# ROS-Robot-Controller.net
KiCad netlist of a schematic drawn in Altium Designer
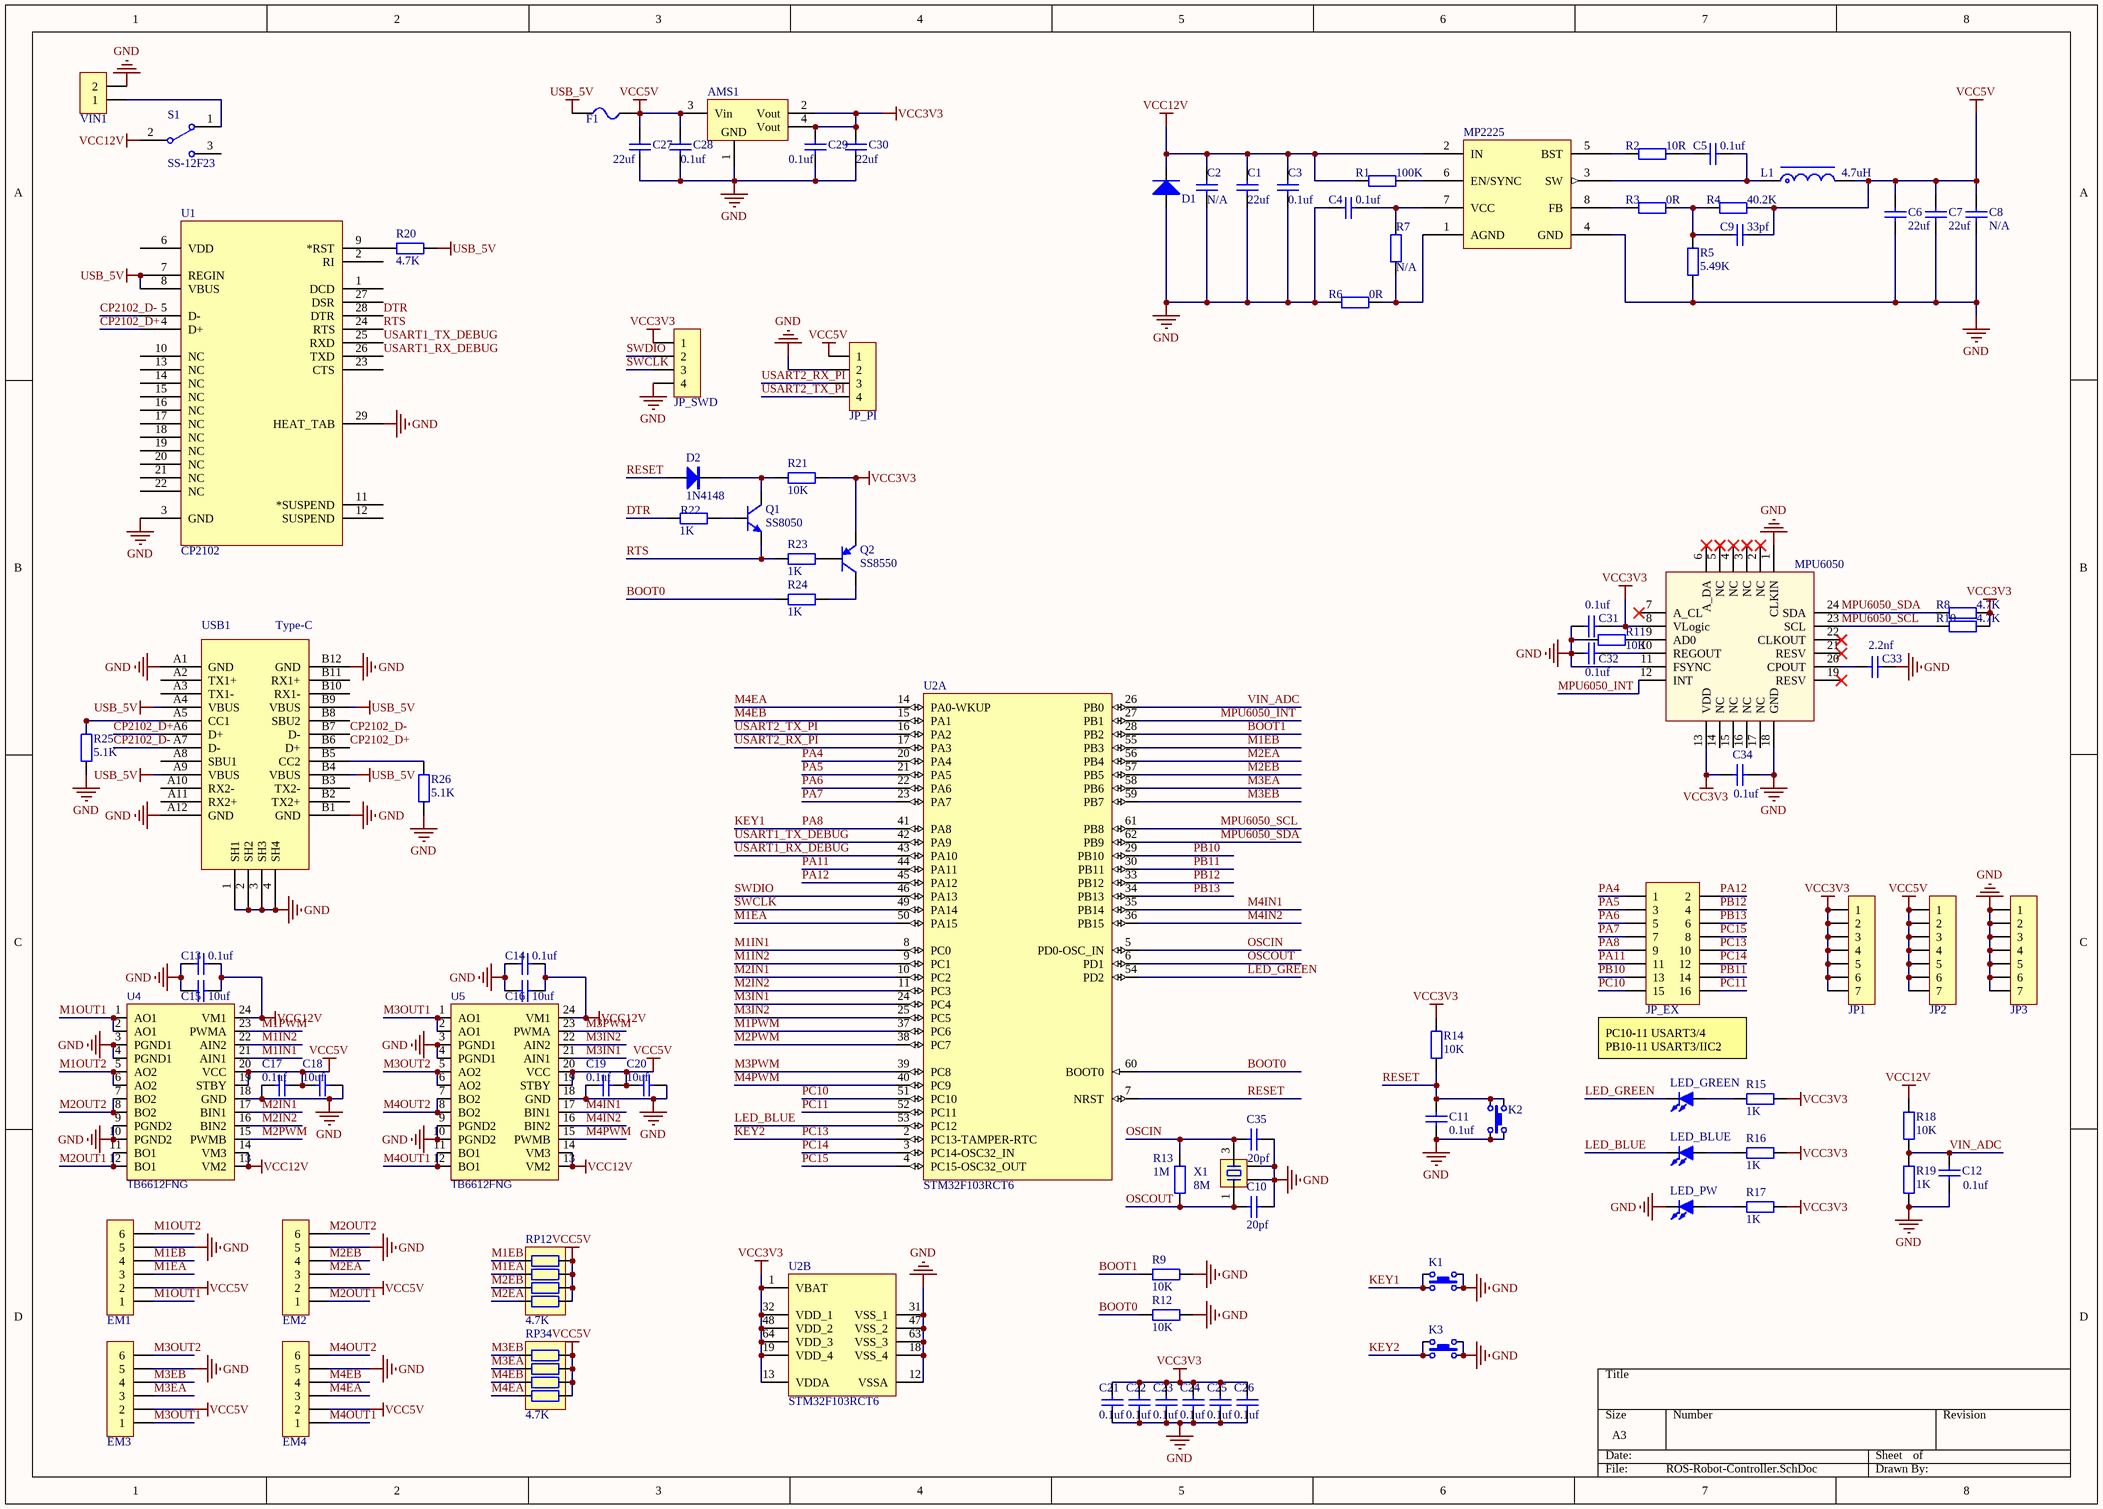
[diagram p0: ROS-Robot-Controller.SchDoc]

(export (version "E")
  (design (tool "Eeschema 10.0.6"))
  (components
    (comp (ref "AMS1")
      (value "AMS1117-3V3")
      (footprint "SOT223_L")
      (description "三端稳压芯片")
      (libsource (lib "1.1 - 电源类芯片") (part "AMS1117"))
    )
    (comp (ref "C1")
      (value "22uf")
      (footprint "C1206_L")
      (description "贴片电容")
      (libsource (lib "0.1 - 电阻-电容-电感-电位器") (part "C"))
    )
    (comp (ref "C2")
      (value "N/A")
      (footprint "C1206_L")
      (description "贴片电容")
      (libsource (lib "0.1 - 电阻-电容-电感-电位器") (part "C"))
    )
    (comp (ref "C3")
      (value "0.1uf")
      (footprint "C0603_L")
      (description "贴片电容")
      (libsource (lib "0.1 - 电阻-电容-电感-电位器") (part "C"))
    )
    (comp (ref "C4")
      (value "0.1uf")
      (footprint "C0603_L")
      (description "贴片电容")
      (libsource (lib "0.1 - 电阻-电容-电感-电位器") (part "C"))
    )
    (comp (ref "C5")
      (value "0.1uf")
      (footprint "C0603_L")
      (description "贴片电容")
      (libsource (lib "0.1 - 电阻-电容-电感-电位器") (part "C"))
    )
    (comp (ref "C6")
      (value "22uf")
      (footprint "C0805_L")
      (description "贴片电容")
      (libsource (lib "0.1 - 电阻-电容-电感-电位器") (part "C"))
    )
    (comp (ref "C7")
      (value "22uf")
      (footprint "C0805_L")
      (description "贴片电容")
      (libsource (lib "0.1 - 电阻-电容-电感-电位器") (part "C"))
    )
    (comp (ref "C8")
      (value "N/A")
      (footprint "C0805_L")
      (description "贴片电容")
      (libsource (lib "0.1 - 电阻-电容-电感-电位器") (part "C"))
    )
    (comp (ref "C9")
      (value "33pf")
      (footprint "C0603_L")
      (description "贴片电容")
      (libsource (lib "0.1 - 电阻-电容-电感-电位器") (part "C"))
    )
    (comp (ref "C10")
      (value "20pf")
      (footprint "C0402_L")
      (description "贴片电容")
      (libsource (lib "0.1 - 电阻-电容-电感-电位器") (part "C"))
    )
    (comp (ref "C11")
      (value "0.1uf")
      (footprint "C0402_L")
      (description "贴片电容")
      (libsource (lib "0.1 - 电阻-电容-电感-电位器") (part "C"))
    )
    (comp (ref "C12")
      (value "0.1uf")
      (footprint "C0603_L")
      (description "贴片电容")
      (libsource (lib "0.1 - 电阻-电容-电感-电位器") (part "C"))
    )
    (comp (ref "C13")
      (value "0.1uf")
      (footprint "C0603_L")
      (description "贴片电容")
      (libsource (lib "0.1 - 电阻-电容-电感-电位器") (part "C"))
    )
    (comp (ref "C14")
      (value "0.1uf")
      (footprint "C0603_L")
      (description "贴片电容")
      (libsource (lib "0.1 - 电阻-电容-电感-电位器") (part "C"))
    )
    (comp (ref "C15")
      (value "10uf")
      (footprint "C0603_L")
      (description "贴片电容")
      (libsource (lib "0.1 - 电阻-电容-电感-电位器") (part "C"))
    )
    (comp (ref "C16")
      (value "10uf")
      (footprint "C0603_L")
      (description "贴片电容")
      (libsource (lib "0.1 - 电阻-电容-电感-电位器") (part "C"))
    )
    (comp (ref "C17")
      (value "0.1uf")
      (footprint "C0402_L")
      (description "贴片电容")
      (libsource (lib "0.1 - 电阻-电容-电感-电位器") (part "C"))
    )
    (comp (ref "C18")
      (value "10uf")
      (footprint "C0402_L")
      (description "贴片电容")
      (libsource (lib "0.1 - 电阻-电容-电感-电位器") (part "C"))
    )
    (comp (ref "C19")
      (value "0.1uf")
      (footprint "C0402_L")
      (description "贴片电容")
      (libsource (lib "0.1 - 电阻-电容-电感-电位器") (part "C"))
    )
    (comp (ref "C20")
      (value "10uf")
      (footprint "C0402_L")
      (description "贴片电容")
      (libsource (lib "0.1 - 电阻-电容-电感-电位器") (part "C"))
    )
    (comp (ref "C21")
      (value "0.1uf")
      (footprint "C0402_L")
      (description "贴片电容")
      (libsource (lib "0.1 - 电阻-电容-电感-电位器") (part "C"))
    )
    (comp (ref "C22")
      (value "0.1uf")
      (footprint "C0402_L")
      (description "贴片电容")
      (libsource (lib "0.1 - 电阻-电容-电感-电位器") (part "C"))
    )
    (comp (ref "C23")
      (value "0.1uf")
      (footprint "C0402_L")
      (description "贴片电容")
      (libsource (lib "0.1 - 电阻-电容-电感-电位器") (part "C"))
    )
    (comp (ref "C24")
      (value "0.1uf")
      (footprint "C0402_L")
      (description "贴片电容")
      (libsource (lib "0.1 - 电阻-电容-电感-电位器") (part "C"))
    )
    (comp (ref "C25")
      (value "0.1uf")
      (footprint "C0402_L")
      (description "贴片电容")
      (libsource (lib "0.1 - 电阻-电容-电感-电位器") (part "C"))
    )
    (comp (ref "C26")
      (value "0.1uf")
      (footprint "C0402_L")
      (description "贴片电容")
      (libsource (lib "0.1 - 电阻-电容-电感-电位器") (part "C"))
    )
    (comp (ref "C27")
      (value "22uf")
      (footprint "C0603_L")
      (description "贴片电容")
      (libsource (lib "0.1 - 电阻-电容-电感-电位器") (part "C"))
    )
    (comp (ref "C28")
      (value "0.1uf")
      (footprint "C0603_L")
      (description "贴片电容")
      (libsource (lib "0.1 - 电阻-电容-电感-电位器") (part "C"))
    )
    (comp (ref "C29")
      (value "0.1uf")
      (footprint "C0603_L")
      (description "贴片电容")
      (libsource (lib "0.1 - 电阻-电容-电感-电位器") (part "C"))
    )
    (comp (ref "C30")
      (value "22uf")
      (footprint "C0603_L")
      (description "贴片电容")
      (libsource (lib "0.1 - 电阻-电容-电感-电位器") (part "C"))
    )
    (comp (ref "C31")
      (value "0.1uf")
      (footprint "C0402_L")
      (description "贴片电容")
      (libsource (lib "0.1 - 电阻-电容-电感-电位器") (part "C"))
    )
    (comp (ref "C32")
      (value "0.1uf")
      (footprint "C0402_L")
      (description "贴片电容")
      (libsource (lib "0.1 - 电阻-电容-电感-电位器") (part "C"))
    )
    (comp (ref "C33")
      (value "2.2nf")
      (footprint "C0402_L")
      (description "贴片电容")
      (libsource (lib "0.1 - 电阻-电容-电感-电位器") (part "C"))
    )
    (comp (ref "C34")
      (value "0.1uf")
      (footprint "C0402_L")
      (description "贴片电容")
      (libsource (lib "0.1 - 电阻-电容-电感-电位器") (part "C"))
    )
    (comp (ref "C35")
      (value "20pf")
      (footprint "C0402_L")
      (description "贴片电容")
      (libsource (lib "0.1 - 电阻-电容-电感-电位器") (part "C"))
    )
    (comp (ref "D1")
      (value "SMAJ12A")
      (footprint "SMA")
      (description "TVS通用")
      (libsource (lib "0.2 - 二极管-TVS-整流桥") (part "TVS"))
    )
    (comp (ref "D2")
      (value "1N4148")
      (footprint "SOD-323")
      (description "开关二极管")
      (libsource (lib "0.2 - 二极管-TVS-整流桥") (part "1N4148"))
    )
    (comp (ref "EM1")
      (value "HDR-1X6")
      (footprint "XH2.54-LI-6P")
      (description "6P接插件")
      (libsource (lib "5.4 - 接插件-脚距2.54 (100mil) ") (part "Header 6"))
    )
    (comp (ref "EM2")
      (value "HDR-1X6")
      (footprint "XH2.54-LI-6P")
      (description "6P接插件")
      (libsource (lib "5.4 - 接插件-脚距2.54 (100mil) ") (part "Header 6"))
    )
    (comp (ref "EM3")
      (value "HDR-1X6")
      (footprint "XH2.54-LI-6P")
      (description "6P接插件")
      (libsource (lib "5.4 - 接插件-脚距2.54 (100mil) ") (part "Header 6"))
    )
    (comp (ref "EM4")
      (value "HDR-1X6")
      (footprint "XH2.54-LI-6P")
      (description "6P接插件")
      (libsource (lib "5.4 - 接插件-脚距2.54 (100mil) ") (part "Header 6"))
    )
    (comp (ref "F1")
      (value "MSMD200-8V 2A")
      (footprint "FU 0603")
      (description "贴片保险丝")
      (libsource (lib "0.5 - 保险丝-晶振-光耦") (part "FU"))
    )
    (comp (ref "JP1")
      (value "HDR-1X7")
      (footprint "HDR2.54-LI-7P")
      (description "7P接插件")
      (libsource (lib "5.4 - 接插件-脚距2.54 (100mil) ") (part "Header 7"))
    )
    (comp (ref "JP2")
      (value "HDR-1X7")
      (footprint "HDR2.54-LI-7P")
      (description "7P接插件")
      (libsource (lib "5.4 - 接插件-脚距2.54 (100mil) ") (part "Header 7"))
    )
    (comp (ref "JP3")
      (value "HDR-1X7")
      (footprint "HDR2.54-LI-7P")
      (description "7P接插件")
      (libsource (lib "5.4 - 接插件-脚距2.54 (100mil) ") (part "Header 7"))
    )
    (comp (ref "JP_EX")
      (value "Header 8X2")
      (footprint "HDR2.54-LI-2x8P")
      (description "8*2P接插件")
      (libsource (lib "5.4 - 接插件-脚距2.54 (100mil) ") (part "Header 8X2"))
    )
    (comp (ref "JP_PI")
      (value "HDR-1X4")
      (footprint "HDR2.54-LI-4P")
      (description "4P接插件")
      (libsource (lib "5.4 - 接插件-脚距2.54 (100mil) ") (part "Header 4"))
    )
    (comp (ref "JP_SWD")
      (value "HDR-1X4")
      (footprint "XH2.54-WI-4P")
      (description "4P接插件")
      (libsource (lib "5.4 - 接插件-脚距2.54 (100mil) ") (part "Header 4"))
    )
    (comp (ref "K1")
      (value "TACT 4P")
      (footprint "SW-SMD_4P-L4.2-W3.3-P2.15-LS5.1")
      (description "Button")
      (libsource (lib "KitSprout") (part "ButtonTACT"))
    )
    (comp (ref "K2")
      (value "TACT 4P")
      (footprint "SW-SMD_4P-L4.2-W3.3-P2.15-LS5.1")
      (description "Button")
      (libsource (lib "KitSprout") (part "ButtonTACT"))
    )
    (comp (ref "K3")
      (value "TACT 4P")
      (footprint "SW-SMD_4P-L4.2-W3.3-P2.15-LS5.1")
      (description "Button")
      (libsource (lib "KitSprout") (part "ButtonTACT"))
    )
    (comp (ref "L1")
      (value "4.7uH")
      (footprint "L-SMD-0630")
      (description "一体成型电感")
      (libsource (lib "0.1 - 电阻-电容-电感-电位器") (part "L-Molding Choke"))
    )
    (comp (ref "LED_BLUE")
      (value "红色")
      (footprint "LED_0402_RED")
      (description "贴片LED")
      (libsource (lib "0.3 - LED发光二极管") (part "LED-SMD"))
    )
    (comp (ref "LED_GREEN")
      (value "红色")
      (footprint "LED_0402_RED")
      (description "贴片LED")
      (libsource (lib "0.3 - LED发光二极管") (part "LED-SMD"))
    )
    (comp (ref "LED_PW")
      (value "红色")
      (footprint "LED_0402_RED")
      (description "贴片LED")
      (libsource (lib "0.3 - LED发光二极管") (part "LED-SMD"))
    )
    (comp (ref "MP2225")
      (value "MP2225")
      (footprint "TSOT23-8_MP2225_MNP")
      (libsource (lib "MP2225") (part "MP2225修改版"))
    )
    (comp (ref "Q1")
      (value "SS8050")
      (footprint "SOT23-3N")
      (description "高频放大-NPN型")
      (libsource (lib "0.4 - 三极管-场效应管-可控硅") (part "8050-SMD"))
    )
    (comp (ref "Q2")
      (value "SS8550")
      (footprint "SOT23-3N")
      (description "高频放大-PNP型")
      (libsource (lib "0.4 - 三极管-场效应管-可控硅") (part "8550-SMD"))
    )
    (comp (ref "R1")
      (value "100K")
      (footprint "R0603_L")
      (description "贴片电阻")
      (libsource (lib "0.1 - 电阻-电容-电感-电位器") (part "R"))
    )
    (comp (ref "R2")
      (value "10R")
      (footprint "R0603_L")
      (description "贴片电阻")
      (libsource (lib "0.1 - 电阻-电容-电感-电位器") (part "R"))
    )
    (comp (ref "R3")
      (value "0R")
      (footprint "R0603_L")
      (description "贴片电阻")
      (libsource (lib "0.1 - 电阻-电容-电感-电位器") (part "R"))
    )
    (comp (ref "R4")
      (value "40.2K")
      (footprint "R0603_L")
      (description "贴片电阻")
      (libsource (lib "0.1 - 电阻-电容-电感-电位器") (part "R"))
    )
    (comp (ref "R5")
      (value "5.49K")
      (footprint "R0603_L")
      (description "贴片电阻")
      (libsource (lib "0.1 - 电阻-电容-电感-电位器") (part "R"))
    )
    (comp (ref "R6")
      (value "0R")
      (footprint "R0603_L")
      (description "贴片电阻")
      (libsource (lib "0.1 - 电阻-电容-电感-电位器") (part "R"))
    )
    (comp (ref "R7")
      (value "N/A")
      (footprint "R0603_L")
      (description "贴片电阻")
      (libsource (lib "0.1 - 电阻-电容-电感-电位器") (part "R"))
    )
    (comp (ref "R8")
      (value "4.7K")
      (footprint "R0402_L")
      (description "贴片电阻")
      (libsource (lib "0.1 - 电阻-电容-电感-电位器") (part "R"))
    )
    (comp (ref "R9")
      (value "10K")
      (footprint "R0402_L")
      (description "贴片电阻")
      (libsource (lib "0.1 - 电阻-电容-电感-电位器") (part "R"))
    )
    (comp (ref "R10")
      (value "4.7K")
      (footprint "R0402_L")
      (description "贴片电阻")
      (libsource (lib "0.1 - 电阻-电容-电感-电位器") (part "R"))
    )
    (comp (ref "R11")
      (value "10K")
      (footprint "R0402_L")
      (description "贴片电阻")
      (libsource (lib "0.1 - 电阻-电容-电感-电位器") (part "R"))
    )
    (comp (ref "R12")
      (value "10K")
      (footprint "R0402_L")
      (description "贴片电阻")
      (libsource (lib "0.1 - 电阻-电容-电感-电位器") (part "R"))
    )
    (comp (ref "R13")
      (value "1M")
      (footprint "R0402_L")
      (description "贴片电阻")
      (libsource (lib "0.1 - 电阻-电容-电感-电位器") (part "R"))
    )
    (comp (ref "R14")
      (value "10K")
      (footprint "R0402_L")
      (description "贴片电阻")
      (libsource (lib "0.1 - 电阻-电容-电感-电位器") (part "R"))
    )
    (comp (ref "R15")
      (value "1K")
      (footprint "R0402_L")
      (description "贴片电阻")
      (libsource (lib "0.1 - 电阻-电容-电感-电位器") (part "R"))
    )
    (comp (ref "R16")
      (value "1K")
      (footprint "R0402_L")
      (description "贴片电阻")
      (libsource (lib "0.1 - 电阻-电容-电感-电位器") (part "R"))
    )
    (comp (ref "R17")
      (value "1K")
      (footprint "R0402_L")
      (description "贴片电阻")
      (libsource (lib "0.1 - 电阻-电容-电感-电位器") (part "R"))
    )
    (comp (ref "R18")
      (value "10K")
      (footprint "R0603_L")
      (description "贴片电阻")
      (libsource (lib "0.1 - 电阻-电容-电感-电位器") (part "R"))
    )
    (comp (ref "R19")
      (value "1K")
      (footprint "R0603_L")
      (description "贴片电阻")
      (libsource (lib "0.1 - 电阻-电容-电感-电位器") (part "R"))
    )
    (comp (ref "R20")
      (value "4.7K")
      (footprint "R0402_L")
      (description "贴片电阻")
      (libsource (lib "0.1 - 电阻-电容-电感-电位器") (part "R"))
    )
    (comp (ref "R21")
      (value "10K")
      (footprint "R0402_L")
      (description "贴片电阻")
      (libsource (lib "0.1 - 电阻-电容-电感-电位器") (part "R"))
    )
    (comp (ref "R22")
      (value "1K")
      (footprint "R0402_L")
      (description "贴片电阻")
      (libsource (lib "0.1 - 电阻-电容-电感-电位器") (part "R"))
    )
    (comp (ref "R23")
      (value "1K")
      (footprint "R0402_L")
      (description "贴片电阻")
      (libsource (lib "0.1 - 电阻-电容-电感-电位器") (part "R"))
    )
    (comp (ref "R24")
      (value "1K")
      (footprint "R0402_L")
      (description "贴片电阻")
      (libsource (lib "0.1 - 电阻-电容-电感-电位器") (part "R"))
    )
    (comp (ref "R25")
      (value "5.1K")
      (footprint "R0402_L")
      (description "贴片电阻")
      (libsource (lib "0.1 - 电阻-电容-电感-电位器") (part "R"))
    )
    (comp (ref "R26")
      (value "5.1K")
      (footprint "R0402_L")
      (description "贴片电阻")
      (libsource (lib "0.1 - 电阻-电容-电感-电位器") (part "R"))
    )
    (comp (ref "RP12")
      (value "4.7K")
      (footprint "RCA-8P4R-0402")
      (description "贴片4P排阻")
      (libsource (lib "0.1 - 电阻-电容-电感-电位器") (part "R-8P4R"))
    )
    (comp (ref "RP34")
      (value "4.7K")
      (footprint "RCA-8P4R-0402")
      (description "贴片4P排阻")
      (libsource (lib "0.1 - 电阻-电容-电感-电位器") (part "R-8P4R"))
    )
    (comp (ref "S1")
      (value "SS-12F23")
      (footprint "SS-12D10")
      (description "1路波动开关")
      (libsource (lib "0.7 - 常用按键-开关-蜂鸣器-电池-测试点") (part "SSW-1P"))
    )
    (comp (ref "U1")
      (value "CP2102")
      (footprint "QFN-28")
      (description "USB转TTL")
      (libsource (lib "mLib") (part "CP2102"))
    )
    (comp (ref "U2")
      (value "STM32F103RCT6")
      (footprint "LQFP64_N")
      (libsource (lib "2.4 - STM32 F1系列单片机") (part "STM32F103RCT6"))
    )
    (comp (ref "U3")
      (value "MPU6050")
      (footprint "QFN-24")
      (description "六轴传感器")
      (libsource (lib "mLib") (part "MPU6050"))
    )
    (comp (ref "U4")
      (value "TB6612FNG")
      (footprint "SSOP24_M")
      (description "电机驱动")
      (libsource (lib "1.0 - 常见芯片") (part "TB6612FNG"))
    )
    (comp (ref "U5")
      (value "TB6612FNG")
      (footprint "SSOP24_M")
      (description "电机驱动")
      (libsource (lib "1.0 - 常见芯片") (part "TB6612FNG"))
    )
    (comp (ref "USB1")
      (value "Type-C")
      (footprint "Type-C-TOP")
      (libsource (lib "MyPcbLib") (part "USB-Type-C-TOP"))
    )
    (comp (ref "VIN1")
      (value "HDR-1X2")
      (footprint "KF301-5.0-2P")
      (description "2P接插件")
      (libsource (lib "6.0 - 接插件-脚距5.0") (part "Header 2"))
    )
    (comp (ref "X1")
      (value "8M")
      (footprint "OSC 3225-4P")
      (description "4脚无源晶振")
      (libsource (lib "0.5 - 保险丝-晶振-光耦") (part "XTAL-4P"))
    )
  )
  (nets
    (net (code "1") (name "/BOOT0") (class "Default")
      (node (ref "R12") (pin "1") (pinfunction "1_1") (pintype "passive"))
      (node (ref "R24") (pin "2") (pinfunction "2_2") (pintype "passive"))
      (node (ref "U2") (pin "60") (pinfunction "BOOT0_60") (pintype "input"))
    )
    (net (code "2") (name "/BOOT1") (class "Default")
      (node (ref "R9") (pin "1") (pinfunction "1_1") (pintype "passive"))
      (node (ref "U2") (pin "28") (pinfunction "PB2_28") (pintype "bidirectional"))
    )
    (net (code "3") (name "/CP2102_D+") (class "Default")
      (node (ref "U1") (pin "4") (pinfunction "D+_4") (pintype "passive"))
      (node (ref "USB1") (pin "A6") (pinfunction "D+_A6") (pintype "passive"))
      (node (ref "USB1") (pin "B6") (pinfunction "D+_B6") (pintype "passive"))
    )
    (net (code "4") (name "/CP2102_D-") (class "Default")
      (node (ref "U1") (pin "5") (pinfunction "D-_5") (pintype "passive"))
      (node (ref "USB1") (pin "A7") (pinfunction "D-_A7") (pintype "passive"))
      (node (ref "USB1") (pin "B7") (pinfunction "D-_B7") (pintype "passive"))
    )
    (net (code "5") (name "/DTR") (class "Default")
      (node (ref "R22") (pin "1") (pinfunction "1_1") (pintype "passive"))
      (node (ref "U1") (pin "28") (pinfunction "DTR_28") (pintype "passive"))
    )
    (net (code "6") (name "/KEY1") (class "Default")
      (node (ref "JP_EX") (pin "9") (pinfunction "9_9") (pintype "passive"))
      (node (ref "K1") (pin "1") (pinfunction "1_1") (pintype "passive"))
      (node (ref "K1") (pin "3") (pinfunction "3_3") (pintype "passive"))
      (node (ref "U2") (pin "41") (pinfunction "PA8_41") (pintype "bidirectional"))
    )
    (net (code "7") (name "/KEY2") (class "Default")
      (node (ref "JP_EX") (pin "10") (pinfunction "10_10") (pintype "passive"))
      (node (ref "K3") (pin "1") (pinfunction "1_1") (pintype "passive"))
      (node (ref "K3") (pin "3") (pinfunction "3_3") (pintype "passive"))
      (node (ref "U2") (pin "2") (pinfunction "PC13-TAMPER-RTC_2") (pintype "bidirectional"))
    )
    (net (code "8") (name "/LED_BLUE") (class "Default")
      (node (ref "LED_BLUE") (pin "2") (pinfunction "K_2") (pintype "passive"))
      (node (ref "U2") (pin "53") (pinfunction "PC12_53") (pintype "bidirectional"))
    )
    (net (code "9") (name "/LED_GREEN") (class "Default")
      (node (ref "LED_GREEN") (pin "2") (pinfunction "K_2") (pintype "passive"))
      (node (ref "U2") (pin "54") (pinfunction "PD2_54") (pintype "bidirectional"))
    )
    (net (code "10") (name "/M1EA") (class "Default")
      (node (ref "EM1") (pin "3") (pinfunction "3_3") (pintype "passive"))
      (node (ref "RP12") (pin "2") (pinfunction "2_2") (pintype "passive"))
      (node (ref "U2") (pin "50") (pinfunction "PA15_50") (pintype "bidirectional"))
    )
    (net (code "11") (name "/M1EB") (class "Default")
      (node (ref "EM1") (pin "4") (pinfunction "4_4") (pintype "passive"))
      (node (ref "RP12") (pin "1") (pinfunction "1_1") (pintype "passive"))
      (node (ref "U2") (pin "55") (pinfunction "PB3_55") (pintype "bidirectional"))
    )
    (net (code "12") (name "/M1IN1") (class "Default")
      (node (ref "U2") (pin "8") (pinfunction "PC0_8") (pintype "bidirectional"))
      (node (ref "U4") (pin "21") (pinfunction "AIN1_21") (pintype "passive"))
    )
    (net (code "13") (name "/M1IN2") (class "Default")
      (node (ref "U2") (pin "9") (pinfunction "PC1_9") (pintype "bidirectional"))
      (node (ref "U4") (pin "22") (pinfunction "AIN2_22") (pintype "passive"))
    )
    (net (code "14") (name "/M1OUT1") (class "Default")
      (node (ref "EM1") (pin "1") (pinfunction "1_1") (pintype "passive"))
      (node (ref "U4") (pin "1") (pinfunction "AO1_1") (pintype "passive"))
      (node (ref "U4") (pin "2") (pinfunction "AO1_2") (pintype "passive"))
    )
    (net (code "15") (name "/M1OUT2") (class "Default")
      (node (ref "EM1") (pin "6") (pinfunction "6_6") (pintype "passive"))
      (node (ref "U4") (pin "5") (pinfunction "AO2_5") (pintype "passive"))
      (node (ref "U4") (pin "6") (pinfunction "AO2_6") (pintype "passive"))
    )
    (net (code "16") (name "/M1PWM") (class "Default")
      (node (ref "U2") (pin "37") (pinfunction "PC6_37") (pintype "bidirectional"))
      (node (ref "U4") (pin "23") (pinfunction "PWMA_23") (pintype "passive"))
    )
    (net (code "17") (name "/M2EA") (class "Default")
      (node (ref "EM2") (pin "3") (pinfunction "3_3") (pintype "passive"))
      (node (ref "RP12") (pin "4") (pinfunction "4_4") (pintype "passive"))
      (node (ref "U2") (pin "56") (pinfunction "PB4_56") (pintype "bidirectional"))
    )
    (net (code "18") (name "/M2EB") (class "Default")
      (node (ref "EM2") (pin "4") (pinfunction "4_4") (pintype "passive"))
      (node (ref "RP12") (pin "3") (pinfunction "3_3") (pintype "passive"))
      (node (ref "U2") (pin "57") (pinfunction "PB5_57") (pintype "bidirectional"))
    )
    (net (code "19") (name "/M2IN1") (class "Default")
      (node (ref "U2") (pin "10") (pinfunction "PC2_10") (pintype "bidirectional"))
      (node (ref "U4") (pin "17") (pinfunction "BIN1_17") (pintype "passive"))
    )
    (net (code "20") (name "/M2IN2") (class "Default")
      (node (ref "U2") (pin "11") (pinfunction "PC3_11") (pintype "bidirectional"))
      (node (ref "U4") (pin "16") (pinfunction "BIN2_16") (pintype "passive"))
    )
    (net (code "21") (name "/M2OUT1") (class "Default")
      (node (ref "EM2") (pin "1") (pinfunction "1_1") (pintype "passive"))
      (node (ref "U4") (pin "11") (pinfunction "BO1_11") (pintype "passive"))
      (node (ref "U4") (pin "12") (pinfunction "BO1_12") (pintype "passive"))
    )
    (net (code "22") (name "/M2OUT2") (class "Default")
      (node (ref "EM2") (pin "6") (pinfunction "6_6") (pintype "passive"))
      (node (ref "U4") (pin "7") (pinfunction "BO2_7") (pintype "passive"))
      (node (ref "U4") (pin "8") (pinfunction "BO2_8") (pintype "passive"))
    )
    (net (code "23") (name "/M2PWM") (class "Default")
      (node (ref "U2") (pin "38") (pinfunction "PC7_38") (pintype "bidirectional"))
      (node (ref "U4") (pin "15") (pinfunction "PWMB_15") (pintype "passive"))
    )
    (net (code "24") (name "/M3EA") (class "Default")
      (node (ref "EM3") (pin "3") (pinfunction "3_3") (pintype "passive"))
      (node (ref "RP34") (pin "2") (pinfunction "2_2") (pintype "passive"))
      (node (ref "U2") (pin "58") (pinfunction "PB6_58") (pintype "bidirectional"))
    )
    (net (code "25") (name "/M3EB") (class "Default")
      (node (ref "EM3") (pin "4") (pinfunction "4_4") (pintype "passive"))
      (node (ref "RP34") (pin "1") (pinfunction "1_1") (pintype "passive"))
      (node (ref "U2") (pin "59") (pinfunction "PB7_59") (pintype "bidirectional"))
    )
    (net (code "26") (name "/M3IN1") (class "Default")
      (node (ref "U2") (pin "24") (pinfunction "PC4_24") (pintype "bidirectional"))
      (node (ref "U5") (pin "21") (pinfunction "AIN1_21") (pintype "passive"))
    )
    (net (code "27") (name "/M3IN2") (class "Default")
      (node (ref "U2") (pin "25") (pinfunction "PC5_25") (pintype "bidirectional"))
      (node (ref "U5") (pin "22") (pinfunction "AIN2_22") (pintype "passive"))
    )
    (net (code "28") (name "/M3OUT1") (class "Default")
      (node (ref "EM3") (pin "1") (pinfunction "1_1") (pintype "passive"))
      (node (ref "U5") (pin "1") (pinfunction "AO1_1") (pintype "passive"))
      (node (ref "U5") (pin "2") (pinfunction "AO1_2") (pintype "passive"))
    )
    (net (code "29") (name "/M3OUT2") (class "Default")
      (node (ref "EM3") (pin "6") (pinfunction "6_6") (pintype "passive"))
      (node (ref "U5") (pin "5") (pinfunction "AO2_5") (pintype "passive"))
      (node (ref "U5") (pin "6") (pinfunction "AO2_6") (pintype "passive"))
    )
    (net (code "30") (name "/M3PWM") (class "Default")
      (node (ref "U2") (pin "39") (pinfunction "PC8_39") (pintype "bidirectional"))
      (node (ref "U5") (pin "23") (pinfunction "PWMA_23") (pintype "passive"))
    )
    (net (code "31") (name "/M4EA") (class "Default")
      (node (ref "EM4") (pin "3") (pinfunction "3_3") (pintype "passive"))
      (node (ref "RP34") (pin "4") (pinfunction "4_4") (pintype "passive"))
      (node (ref "U2") (pin "14") (pinfunction "PA0-WKUP_14") (pintype "bidirectional"))
    )
    (net (code "32") (name "/M4EB") (class "Default")
      (node (ref "EM4") (pin "4") (pinfunction "4_4") (pintype "passive"))
      (node (ref "RP34") (pin "3") (pinfunction "3_3") (pintype "passive"))
      (node (ref "U2") (pin "15") (pinfunction "PA1_15") (pintype "bidirectional"))
    )
    (net (code "33") (name "/M4IN1") (class "Default")
      (node (ref "U2") (pin "35") (pinfunction "PB14_35") (pintype "bidirectional"))
      (node (ref "U5") (pin "17") (pinfunction "BIN1_17") (pintype "passive"))
    )
    (net (code "34") (name "/M4IN2") (class "Default")
      (node (ref "U2") (pin "36") (pinfunction "PB15_36") (pintype "bidirectional"))
      (node (ref "U5") (pin "16") (pinfunction "BIN2_16") (pintype "passive"))
    )
    (net (code "35") (name "/M4OUT1") (class "Default")
      (node (ref "EM4") (pin "1") (pinfunction "1_1") (pintype "passive"))
      (node (ref "U5") (pin "11") (pinfunction "BO1_11") (pintype "passive"))
      (node (ref "U5") (pin "12") (pinfunction "BO1_12") (pintype "passive"))
    )
    (net (code "36") (name "/M4OUT2") (class "Default")
      (node (ref "EM4") (pin "6") (pinfunction "6_6") (pintype "passive"))
      (node (ref "U5") (pin "7") (pinfunction "BO2_7") (pintype "passive"))
      (node (ref "U5") (pin "8") (pinfunction "BO2_8") (pintype "passive"))
    )
    (net (code "37") (name "/M4PWM") (class "Default")
      (node (ref "U2") (pin "40") (pinfunction "PC9_40") (pintype "bidirectional"))
      (node (ref "U5") (pin "15") (pinfunction "PWMB_15") (pintype "passive"))
    )
    (net (code "38") (name "/MPU6050_INT") (class "Default")
      (node (ref "U2") (pin "27") (pinfunction "PB1_27") (pintype "bidirectional"))
      (node (ref "U3") (pin "12") (pinfunction "INT_12") (pintype "passive"))
    )
    (net (code "39") (name "/MPU6050_SCL") (class "Default")
      (node (ref "R10") (pin "1") (pinfunction "1_1") (pintype "passive"))
      (node (ref "U2") (pin "61") (pinfunction "PB8_61") (pintype "bidirectional"))
      (node (ref "U3") (pin "23") (pinfunction "SCL_23") (pintype "passive"))
    )
    (net (code "40") (name "/MPU6050_SDA") (class "Default")
      (node (ref "R8") (pin "1") (pinfunction "1_1") (pintype "passive"))
      (node (ref "U2") (pin "62") (pinfunction "PB9_62") (pintype "bidirectional"))
      (node (ref "U3") (pin "24") (pinfunction "SDA_24") (pintype "passive"))
    )
    (net (code "41") (name "/OSCIN") (class "Default")
      (node (ref "C35") (pin "1") (pinfunction "1_1") (pintype "passive"))
      (node (ref "R13") (pin "2") (pinfunction "2_2") (pintype "passive"))
      (node (ref "U2") (pin "5") (pinfunction "PD0-OSC_IN_5") (pintype "bidirectional"))
      (node (ref "X1") (pin "3") (pinfunction "3_3") (pintype "passive"))
    )
    (net (code "42") (name "/OSCOUT") (class "Default")
      (node (ref "C10") (pin "1") (pinfunction "1_1") (pintype "passive"))
      (node (ref "R13") (pin "1") (pinfunction "1_1") (pintype "passive"))
      (node (ref "U2") (pin "6") (pinfunction "PD1_6") (pintype "bidirectional"))
      (node (ref "X1") (pin "1") (pinfunction "1_1") (pintype "passive"))
    )
    (net (code "43") (name "/PA4") (class "Default")
      (node (ref "JP_EX") (pin "1") (pinfunction "1_1") (pintype "passive"))
      (node (ref "U2") (pin "20") (pinfunction "PA4_20") (pintype "bidirectional"))
    )
    (net (code "44") (name "/PA5") (class "Default")
      (node (ref "JP_EX") (pin "3") (pinfunction "3_3") (pintype "passive"))
      (node (ref "U2") (pin "21") (pinfunction "PA5_21") (pintype "bidirectional"))
    )
    (net (code "45") (name "/PA6") (class "Default")
      (node (ref "JP_EX") (pin "5") (pinfunction "5_5") (pintype "passive"))
      (node (ref "U2") (pin "22") (pinfunction "PA6_22") (pintype "bidirectional"))
    )
    (net (code "46") (name "/PA7") (class "Default")
      (node (ref "JP_EX") (pin "7") (pinfunction "7_7") (pintype "passive"))
      (node (ref "U2") (pin "23") (pinfunction "PA7_23") (pintype "bidirectional"))
    )
    (net (code "47") (name "/PA11") (class "Default")
      (node (ref "JP_EX") (pin "11") (pinfunction "11_11") (pintype "passive"))
      (node (ref "U2") (pin "44") (pinfunction "PA11_44") (pintype "bidirectional"))
    )
    (net (code "48") (name "/PA12") (class "Default")
      (node (ref "JP_EX") (pin "2") (pinfunction "2_2") (pintype "passive"))
      (node (ref "U2") (pin "45") (pinfunction "PA12_45") (pintype "bidirectional"))
    )
    (net (code "49") (name "/PB10") (class "Default")
      (node (ref "JP_EX") (pin "13") (pinfunction "13_13") (pintype "passive"))
      (node (ref "U2") (pin "29") (pinfunction "PB10_29") (pintype "bidirectional"))
    )
    (net (code "50") (name "/PB11") (class "Default")
      (node (ref "JP_EX") (pin "14") (pinfunction "14_14") (pintype "passive"))
      (node (ref "U2") (pin "30") (pinfunction "PB11_30") (pintype "bidirectional"))
    )
    (net (code "51") (name "/PB12") (class "Default")
      (node (ref "JP_EX") (pin "4") (pinfunction "4_4") (pintype "passive"))
      (node (ref "U2") (pin "33") (pinfunction "PB12_33") (pintype "bidirectional"))
    )
    (net (code "52") (name "/PB13") (class "Default")
      (node (ref "JP_EX") (pin "6") (pinfunction "6_6") (pintype "passive"))
      (node (ref "U2") (pin "34") (pinfunction "PB13_34") (pintype "bidirectional"))
    )
    (net (code "53") (name "/PC10") (class "Default")
      (node (ref "JP_EX") (pin "15") (pinfunction "15_15") (pintype "passive"))
      (node (ref "U2") (pin "51") (pinfunction "PC10_51") (pintype "bidirectional"))
    )
    (net (code "54") (name "/PC11") (class "Default")
      (node (ref "JP_EX") (pin "16") (pinfunction "16_16") (pintype "passive"))
      (node (ref "U2") (pin "52") (pinfunction "PC11_52") (pintype "bidirectional"))
    )
    (net (code "55") (name "/PC14") (class "Default")
      (node (ref "JP_EX") (pin "12") (pinfunction "12_12") (pintype "passive"))
      (node (ref "U2") (pin "3") (pinfunction "PC14-OSC32_IN_3") (pintype "bidirectional"))
    )
    (net (code "56") (name "/PC15") (class "Default")
      (node (ref "JP_EX") (pin "8") (pinfunction "8_8") (pintype "passive"))
      (node (ref "U2") (pin "4") (pinfunction "PC15-OSC32_OUT_4") (pintype "bidirectional"))
    )
    (net (code "57") (name "/RESET") (class "Default")
      (node (ref "C11") (pin "2") (pinfunction "2_2") (pintype "passive"))
      (node (ref "D2") (pin "1") (pinfunction "A_1") (pintype "passive"))
      (node (ref "K2") (pin "1") (pinfunction "1_1") (pintype "passive"))
      (node (ref "K2") (pin "3") (pinfunction "3_3") (pintype "passive"))
      (node (ref "R14") (pin "1") (pinfunction "1_1") (pintype "passive"))
      (node (ref "U2") (pin "7") (pinfunction "NRST_7") (pintype "bidirectional"))
    )
    (net (code "58") (name "/RTS") (class "Default")
      (node (ref "Q1") (pin "2") (pinfunction "E_2") (pintype "passive"))
      (node (ref "R23") (pin "1") (pinfunction "1_1") (pintype "passive"))
      (node (ref "U1") (pin "24") (pinfunction "RTS_24") (pintype "passive"))
    )
    (net (code "59") (name "/SWCLK") (class "Default")
      (node (ref "JP_SWD") (pin "3") (pinfunction "3_3") (pintype "passive"))
      (node (ref "U2") (pin "49") (pinfunction "PA14_49") (pintype "bidirectional"))
    )
    (net (code "60") (name "/SWDIO") (class "Default")
      (node (ref "JP_SWD") (pin "2") (pinfunction "2_2") (pintype "passive"))
      (node (ref "U2") (pin "46") (pinfunction "PA13_46") (pintype "bidirectional"))
    )
    (net (code "61") (name "/USART1_RX_DEBUG") (class "Default")
      (node (ref "U1") (pin "26") (pinfunction "TXD_26") (pintype "passive"))
      (node (ref "U2") (pin "43") (pinfunction "PA10_43") (pintype "bidirectional"))
    )
    (net (code "62") (name "/USART1_TX_DEBUG") (class "Default")
      (node (ref "U1") (pin "25") (pinfunction "RXD_25") (pintype "passive"))
      (node (ref "U2") (pin "42") (pinfunction "PA9_42") (pintype "bidirectional"))
    )
    (net (code "63") (name "/USART2_RX_PI") (class "Default")
      (node (ref "JP_PI") (pin "3") (pinfunction "3_3") (pintype "passive"))
      (node (ref "U2") (pin "17") (pinfunction "PA3_17") (pintype "bidirectional"))
    )
    (net (code "64") (name "/USART2_TX_PI") (class "Default")
      (node (ref "JP_PI") (pin "4") (pinfunction "4_4") (pintype "passive"))
      (node (ref "U2") (pin "16") (pinfunction "PA2_16") (pintype "bidirectional"))
    )
    (net (code "65") (name "/VIN_ADC") (class "Default")
      (node (ref "C12") (pin "2") (pinfunction "2_2") (pintype "passive"))
      (node (ref "R18") (pin "1") (pinfunction "1_1") (pintype "passive"))
      (node (ref "R19") (pin "2") (pinfunction "2_2") (pintype "passive"))
      (node (ref "U2") (pin "26") (pinfunction "PB0_26") (pintype "bidirectional"))
    )
    (net (code "66") (name "GND") (class "Default")
      (node (ref "AMS1") (pin "1") (pinfunction "GND_1") (pintype "passive"))
      (node (ref "C1") (pin "1") (pinfunction "1_1") (pintype "passive"))
      (node (ref "C10") (pin "2") (pinfunction "2_2") (pintype "passive"))
      (node (ref "C11") (pin "1") (pinfunction "1_1") (pintype "passive"))
      (node (ref "C12") (pin "1") (pinfunction "1_1") (pintype "passive"))
      (node (ref "C13") (pin "1") (pinfunction "1_1") (pintype "passive"))
      (node (ref "C14") (pin "1") (pinfunction "1_1") (pintype "passive"))
      (node (ref "C15") (pin "1") (pinfunction "1_1") (pintype "passive"))
      (node (ref "C16") (pin "1") (pinfunction "1_1") (pintype "passive"))
      (node (ref "C17") (pin "2") (pinfunction "2_2") (pintype "passive"))
      (node (ref "C18") (pin "1") (pinfunction "1_1") (pintype "passive"))
      (node (ref "C19") (pin "2") (pinfunction "2_2") (pintype "passive"))
      (node (ref "C2") (pin "1") (pinfunction "1_1") (pintype "passive"))
      (node (ref "C20") (pin "1") (pinfunction "1_1") (pintype "passive"))
      (node (ref "C21") (pin "1") (pinfunction "1_1") (pintype "passive"))
      (node (ref "C22") (pin "1") (pinfunction "1_1") (pintype "passive"))
      (node (ref "C23") (pin "1") (pinfunction "1_1") (pintype "passive"))
      (node (ref "C24") (pin "1") (pinfunction "1_1") (pintype "passive"))
      (node (ref "C25") (pin "1") (pinfunction "1_1") (pintype "passive"))
      (node (ref "C26") (pin "1") (pinfunction "1_1") (pintype "passive"))
      (node (ref "C27") (pin "1") (pinfunction "1_1") (pintype "passive"))
      (node (ref "C28") (pin "1") (pinfunction "1_1") (pintype "passive"))
      (node (ref "C29") (pin "1") (pinfunction "1_1") (pintype "passive"))
      (node (ref "C3") (pin "1") (pinfunction "1_1") (pintype "passive"))
      (node (ref "C30") (pin "1") (pinfunction "1_1") (pintype "passive"))
      (node (ref "C31") (pin "1") (pinfunction "1_1") (pintype "passive"))
      (node (ref "C32") (pin "1") (pinfunction "1_1") (pintype "passive"))
      (node (ref "C33") (pin "2") (pinfunction "2_2") (pintype "passive"))
      (node (ref "C34") (pin "2") (pinfunction "2_2") (pintype "passive"))
      (node (ref "C35") (pin "2") (pinfunction "2_2") (pintype "passive"))
      (node (ref "C4") (pin "2") (pinfunction "2_2") (pintype "passive"))
      (node (ref "C6") (pin "1") (pinfunction "1_1") (pintype "passive"))
      (node (ref "C7") (pin "1") (pinfunction "1_1") (pintype "passive"))
      (node (ref "C8") (pin "1") (pinfunction "1_1") (pintype "passive"))
      (node (ref "D1") (pin "1") (pinfunction "A_1") (pintype "passive"))
      (node (ref "EM1") (pin "5") (pinfunction "5_5") (pintype "passive"))
      (node (ref "EM2") (pin "5") (pinfunction "5_5") (pintype "passive"))
      (node (ref "EM3") (pin "5") (pinfunction "5_5") (pintype "passive"))
      (node (ref "EM4") (pin "5") (pinfunction "5_5") (pintype "passive"))
      (node (ref "JP3") (pin "1") (pinfunction "1_1") (pintype "passive"))
      (node (ref "JP3") (pin "2") (pinfunction "2_2") (pintype "passive"))
      (node (ref "JP3") (pin "3") (pinfunction "3_3") (pintype "passive"))
      (node (ref "JP3") (pin "4") (pinfunction "4_4") (pintype "passive"))
      (node (ref "JP3") (pin "5") (pinfunction "5_5") (pintype "passive"))
      (node (ref "JP3") (pin "6") (pinfunction "6_6") (pintype "passive"))
      (node (ref "JP3") (pin "7") (pinfunction "7_7") (pintype "passive"))
      (node (ref "JP_PI") (pin "2") (pinfunction "2_2") (pintype "passive"))
      (node (ref "JP_SWD") (pin "4") (pinfunction "4_4") (pintype "passive"))
      (node (ref "K1") (pin "2") (pinfunction "2_2") (pintype "passive"))
      (node (ref "K1") (pin "4") (pinfunction "4_4") (pintype "passive"))
      (node (ref "K2") (pin "2") (pinfunction "2_2") (pintype "passive"))
      (node (ref "K2") (pin "4") (pinfunction "4_4") (pintype "passive"))
      (node (ref "K3") (pin "2") (pinfunction "2_2") (pintype "passive"))
      (node (ref "K3") (pin "4") (pinfunction "4_4") (pintype "passive"))
      (node (ref "LED_PW") (pin "2") (pinfunction "K_2") (pintype "passive"))
      (node (ref "MP2225") (pin "4") (pinfunction "GND_4") (pintype "power_in"))
      (node (ref "R11") (pin "1") (pinfunction "1_1") (pintype "passive"))
      (node (ref "R12") (pin "2") (pinfunction "2_2") (pintype "passive"))
      (node (ref "R19") (pin "1") (pinfunction "1_1") (pintype "passive"))
      (node (ref "R25") (pin "1") (pinfunction "1_1") (pintype "passive"))
      (node (ref "R26") (pin "1") (pinfunction "1_1") (pintype "passive"))
      (node (ref "R5") (pin "1") (pinfunction "1_1") (pintype "passive"))
      (node (ref "R6") (pin "2") (pinfunction "2_2") (pintype "passive"))
      (node (ref "R9") (pin "2") (pinfunction "2_2") (pintype "passive"))
      (node (ref "U1") (pin "29") (pinfunction "HEAT_TAB_29") (pintype "passive"))
      (node (ref "U1") (pin "3") (pinfunction "GND_3") (pintype "passive"))
      (node (ref "U2") (pin "12") (pinfunction "VSSA_12") (pintype "power_in"))
      (node (ref "U2") (pin "18") (pinfunction "VSS_4_18") (pintype "power_in"))
      (node (ref "U2") (pin "31") (pinfunction "VSS_1_31") (pintype "power_in"))
      (node (ref "U2") (pin "47") (pinfunction "VSS_2_47") (pintype "power_in"))
      (node (ref "U2") (pin "63") (pinfunction "VSS_3_63") (pintype "power_in"))
      (node (ref "U3") (pin "1") (pinfunction "CLKIN_1") (pintype "passive"))
      (node (ref "U3") (pin "11") (pinfunction "FSYNC_11") (pintype "passive"))
      (node (ref "U3") (pin "18") (pinfunction "GND_18") (pintype "passive"))
      (node (ref "U4") (pin "10") (pinfunction "PGND2_10") (pintype "passive"))
      (node (ref "U4") (pin "18") (pinfunction "GND_18") (pintype "passive"))
      (node (ref "U4") (pin "3") (pinfunction "PGND1_3") (pintype "passive"))
      (node (ref "U4") (pin "4") (pinfunction "PGND1_4") (pintype "passive"))
      (node (ref "U4") (pin "9") (pinfunction "PGND2_9") (pintype "passive"))
      (node (ref "U5") (pin "10") (pinfunction "PGND2_10") (pintype "passive"))
      (node (ref "U5") (pin "18") (pinfunction "GND_18") (pintype "passive"))
      (node (ref "U5") (pin "3") (pinfunction "PGND1_3") (pintype "passive"))
      (node (ref "U5") (pin "4") (pinfunction "PGND1_4") (pintype "passive"))
      (node (ref "U5") (pin "9") (pinfunction "PGND2_9") (pintype "passive"))
      (node (ref "USB1") (pin "1") (pinfunction "SH1_1") (pintype "passive"))
      (node (ref "USB1") (pin "2") (pinfunction "SH2_2") (pintype "passive"))
      (node (ref "USB1") (pin "3") (pinfunction "SH3_3") (pintype "passive"))
      (node (ref "USB1") (pin "4") (pinfunction "SH4_4") (pintype "passive"))
      (node (ref "USB1") (pin "A1") (pinfunction "GND_A1") (pintype "passive"))
      (node (ref "USB1") (pin "A12") (pinfunction "GND_A12") (pintype "passive"))
      (node (ref "USB1") (pin "B1") (pinfunction "GND_B1") (pintype "passive"))
      (node (ref "USB1") (pin "B12") (pinfunction "GND_B12") (pintype "passive"))
      (node (ref "VIN1") (pin "2") (pinfunction "2_2") (pintype "passive"))
      (node (ref "X1") (pin "2") (pinfunction "2_2") (pintype "passive"))
      (node (ref "X1") (pin "4") (pinfunction "4_4") (pintype "passive"))
    )
    (net (code "67") (name "Net-(C5-Pad2)") (class "Default")
      (node (ref "C5") (pin "2") (pinfunction "2_2") (pintype "passive"))
      (node (ref "R2") (pin "2") (pinfunction "2_2") (pintype "passive"))
    )
    (net (code "68") (name "Net-(C9-Pad2)") (class "Default")
      (node (ref "C9") (pin "2") (pinfunction "2_2") (pintype "passive"))
      (node (ref "R3") (pin "2") (pinfunction "2_2") (pintype "passive"))
      (node (ref "R4") (pin "1") (pinfunction "1_1") (pintype "passive"))
      (node (ref "R5") (pin "2") (pinfunction "2_2") (pintype "passive"))
    )
    (net (code "69") (name "Net-(D2-K)") (class "Default")
      (node (ref "D2") (pin "2") (pinfunction "K_2") (pintype "passive"))
      (node (ref "Q1") (pin "3") (pinfunction "C_3") (pintype "passive"))
      (node (ref "R21") (pin "2") (pinfunction "2_2") (pintype "passive"))
    )
    (net (code "70") (name "Net-(LED_BLUE-A)") (class "Default")
      (node (ref "LED_BLUE") (pin "1") (pinfunction "A_1") (pintype "passive"))
      (node (ref "R16") (pin "1") (pinfunction "1_1") (pintype "passive"))
    )
    (net (code "71") (name "Net-(LED_GREEN-A)") (class "Default")
      (node (ref "LED_GREEN") (pin "1") (pinfunction "A_1") (pintype "passive"))
      (node (ref "R15") (pin "1") (pinfunction "1_1") (pintype "passive"))
    )
    (net (code "72") (name "Net-(LED_PW-A)") (class "Default")
      (node (ref "LED_PW") (pin "1") (pinfunction "A_1") (pintype "passive"))
      (node (ref "R17") (pin "1") (pinfunction "1_1") (pintype "passive"))
    )
    (net (code "73") (name "Net-(MP2225-AGND)") (class "Default")
      (node (ref "MP2225") (pin "1") (pinfunction "AGND_1") (pintype "power_in"))
      (node (ref "R6") (pin "1") (pinfunction "1_1") (pintype "passive"))
      (node (ref "R7") (pin "1") (pinfunction "1_1") (pintype "passive"))
    )
    (net (code "74") (name "Net-(MP2225-BST)") (class "Default")
      (node (ref "MP2225") (pin "5") (pinfunction "BST_5") (pintype "power_in"))
      (node (ref "R2") (pin "1") (pinfunction "1_1") (pintype "passive"))
    )
    (net (code "75") (name "Net-(MP2225-EN{slash}SYNC)") (class "Default")
      (node (ref "MP2225") (pin "6") (pinfunction "EN/SYNC_6") (pintype "passive"))
      (node (ref "R1") (pin "2") (pinfunction "2_2") (pintype "passive"))
    )
    (net (code "76") (name "Net-(MP2225-FB)") (class "Default")
      (node (ref "MP2225") (pin "8") (pinfunction "FB_8") (pintype "passive"))
      (node (ref "R3") (pin "1") (pinfunction "1_1") (pintype "passive"))
    )
    (net (code "77") (name "Net-(MP2225-SW)") (class "Default")
      (node (ref "C5") (pin "1") (pinfunction "1_1") (pintype "passive"))
      (node (ref "L1") (pin "1") (pinfunction "1_1") (pintype "passive"))
      (node (ref "MP2225") (pin "3") (pinfunction "SW_3") (pintype "output"))
    )
    (net (code "78") (name "Net-(MP2225-VCC)") (class "Default")
      (node (ref "C4") (pin "1") (pinfunction "1_1") (pintype "passive"))
      (node (ref "MP2225") (pin "7") (pinfunction "VCC_7") (pintype "power_in"))
      (node (ref "R7") (pin "2") (pinfunction "2_2") (pintype "passive"))
    )
    (net (code "79") (name "Net-(Q1-B)") (class "Default")
      (node (ref "Q1") (pin "1") (pinfunction "B_1") (pintype "passive"))
      (node (ref "R22") (pin "2") (pinfunction "2_2") (pintype "passive"))
    )
    (net (code "80") (name "Net-(Q2-B)") (class "Default")
      (node (ref "Q2") (pin "1") (pinfunction "B_1") (pintype "passive"))
      (node (ref "R23") (pin "2") (pinfunction "2_2") (pintype "passive"))
    )
    (net (code "81") (name "Net-(Q2-C)") (class "Default")
      (node (ref "Q2") (pin "3") (pinfunction "C_3") (pintype "passive"))
      (node (ref "R24") (pin "1") (pinfunction "1_1") (pintype "passive"))
    )
    (net (code "82") (name "Net-(S1-Pad1)") (class "Default")
      (node (ref "S1") (pin "1") (pinfunction "1_1") (pintype "passive"))
      (node (ref "VIN1") (pin "1") (pinfunction "1_1") (pintype "passive"))
    )
    (net (code "83") (name "Net-(U1-*RST)") (class "Default")
      (node (ref "R20") (pin "1") (pinfunction "1_1") (pintype "passive"))
      (node (ref "U1") (pin "9") (pinfunction "*RST_9") (pintype "passive"))
    )
    (net (code "84") (name "Net-(U3-AD0)") (class "Default")
      (node (ref "R11") (pin "2") (pinfunction "2_2") (pintype "passive"))
      (node (ref "U3") (pin "9") (pinfunction "AD0_9") (pintype "passive"))
    )
    (net (code "85") (name "Net-(U3-CPOUT)") (class "Default")
      (node (ref "C33") (pin "1") (pinfunction "1_1") (pintype "passive"))
      (node (ref "U3") (pin "20") (pinfunction "CPOUT_20") (pintype "passive"))
    )
    (net (code "86") (name "Net-(U3-REGOUT)") (class "Default")
      (node (ref "C32") (pin "2") (pinfunction "2_2") (pintype "passive"))
      (node (ref "U3") (pin "10") (pinfunction "REGOUT_10") (pintype "passive"))
    )
    (net (code "87") (name "Net-(USB1-CC1)") (class "Default")
      (node (ref "R25") (pin "2") (pinfunction "2_2") (pintype "passive"))
      (node (ref "USB1") (pin "A5") (pinfunction "CC1_A5") (pintype "passive"))
    )
    (net (code "88") (name "Net-(USB1-CC2)") (class "Default")
      (node (ref "R26") (pin "2") (pinfunction "2_2") (pintype "passive"))
      (node (ref "USB1") (pin "B5") (pinfunction "CC2_B5") (pintype "passive"))
    )
    (net (code "89") (name "USB_5V") (class "Default")
      (node (ref "F1") (pin "1") (pinfunction "1_1") (pintype "passive"))
      (node (ref "R20") (pin "2") (pinfunction "2_2") (pintype "passive"))
      (node (ref "U1") (pin "7") (pinfunction "REGIN_7") (pintype "passive"))
      (node (ref "U1") (pin "8") (pinfunction "VBUS_8") (pintype "passive"))
      (node (ref "USB1") (pin "A4") (pinfunction "VBUS_A4") (pintype "passive"))
      (node (ref "USB1") (pin "A9") (pinfunction "VBUS_A9") (pintype "passive"))
      (node (ref "USB1") (pin "B4") (pinfunction "VBUS_B4") (pintype "passive"))
      (node (ref "USB1") (pin "B9") (pinfunction "VBUS_B9") (pintype "passive"))
    )
    (net (code "90") (name "VCC3V3") (class "Default")
      (node (ref "AMS1") (pin "2") (pinfunction "Vout_2") (pintype "passive"))
      (node (ref "AMS1") (pin "4") (pinfunction "Vout_4") (pintype "passive"))
      (node (ref "C21") (pin "2") (pinfunction "2_2") (pintype "passive"))
      (node (ref "C22") (pin "2") (pinfunction "2_2") (pintype "passive"))
      (node (ref "C23") (pin "2") (pinfunction "2_2") (pintype "passive"))
      (node (ref "C24") (pin "2") (pinfunction "2_2") (pintype "passive"))
      (node (ref "C25") (pin "2") (pinfunction "2_2") (pintype "passive"))
      (node (ref "C26") (pin "2") (pinfunction "2_2") (pintype "passive"))
      (node (ref "C29") (pin "2") (pinfunction "2_2") (pintype "passive"))
      (node (ref "C30") (pin "2") (pinfunction "2_2") (pintype "passive"))
      (node (ref "C31") (pin "2") (pinfunction "2_2") (pintype "passive"))
      (node (ref "C34") (pin "1") (pinfunction "1_1") (pintype "passive"))
      (node (ref "JP1") (pin "1") (pinfunction "1_1") (pintype "passive"))
      (node (ref "JP1") (pin "2") (pinfunction "2_2") (pintype "passive"))
      (node (ref "JP1") (pin "3") (pinfunction "3_3") (pintype "passive"))
      (node (ref "JP1") (pin "4") (pinfunction "4_4") (pintype "passive"))
      (node (ref "JP1") (pin "5") (pinfunction "5_5") (pintype "passive"))
      (node (ref "JP1") (pin "6") (pinfunction "6_6") (pintype "passive"))
      (node (ref "JP1") (pin "7") (pinfunction "7_7") (pintype "passive"))
      (node (ref "JP_SWD") (pin "1") (pinfunction "1_1") (pintype "passive"))
      (node (ref "Q2") (pin "2") (pinfunction "E_2") (pintype "passive"))
      (node (ref "R10") (pin "2") (pinfunction "2_2") (pintype "passive"))
      (node (ref "R14") (pin "2") (pinfunction "2_2") (pintype "passive"))
      (node (ref "R15") (pin "2") (pinfunction "2_2") (pintype "passive"))
      (node (ref "R16") (pin "2") (pinfunction "2_2") (pintype "passive"))
      (node (ref "R17") (pin "2") (pinfunction "2_2") (pintype "passive"))
      (node (ref "R21") (pin "1") (pinfunction "1_1") (pintype "passive"))
      (node (ref "R8") (pin "2") (pinfunction "2_2") (pintype "passive"))
      (node (ref "U2") (pin "1") (pinfunction "VBAT_1") (pintype "power_in"))
      (node (ref "U2") (pin "13") (pinfunction "VDDA_13") (pintype "power_in"))
      (node (ref "U2") (pin "19") (pinfunction "VDD_4_19") (pintype "power_in"))
      (node (ref "U2") (pin "32") (pinfunction "VDD_1_32") (pintype "power_in"))
      (node (ref "U2") (pin "48") (pinfunction "VDD_2_48") (pintype "power_in"))
      (node (ref "U2") (pin "64") (pinfunction "VDD_3_64") (pintype "power_in"))
      (node (ref "U3") (pin "13") (pinfunction "VDD_13") (pintype "passive"))
      (node (ref "U3") (pin "8") (pinfunction "VLogic_8") (pintype "passive"))
    )
    (net (code "91") (name "VCC5V") (class "Default")
      (node (ref "AMS1") (pin "3") (pinfunction "Vin_3") (pintype "passive"))
      (node (ref "C17") (pin "1") (pinfunction "1_1") (pintype "passive"))
      (node (ref "C18") (pin "2") (pinfunction "2_2") (pintype "passive"))
      (node (ref "C19") (pin "1") (pinfunction "1_1") (pintype "passive"))
      (node (ref "C20") (pin "2") (pinfunction "2_2") (pintype "passive"))
      (node (ref "C27") (pin "2") (pinfunction "2_2") (pintype "passive"))
      (node (ref "C28") (pin "2") (pinfunction "2_2") (pintype "passive"))
      (node (ref "C6") (pin "2") (pinfunction "2_2") (pintype "passive"))
      (node (ref "C7") (pin "2") (pinfunction "2_2") (pintype "passive"))
      (node (ref "C8") (pin "2") (pinfunction "2_2") (pintype "passive"))
      (node (ref "C9") (pin "1") (pinfunction "1_1") (pintype "passive"))
      (node (ref "EM1") (pin "2") (pinfunction "2_2") (pintype "passive"))
      (node (ref "EM2") (pin "2") (pinfunction "2_2") (pintype "passive"))
      (node (ref "EM3") (pin "2") (pinfunction "2_2") (pintype "passive"))
      (node (ref "EM4") (pin "2") (pinfunction "2_2") (pintype "passive"))
      (node (ref "F1") (pin "2") (pinfunction "2_2") (pintype "passive"))
      (node (ref "JP2") (pin "1") (pinfunction "1_1") (pintype "passive"))
      (node (ref "JP2") (pin "2") (pinfunction "2_2") (pintype "passive"))
      (node (ref "JP2") (pin "3") (pinfunction "3_3") (pintype "passive"))
      (node (ref "JP2") (pin "4") (pinfunction "4_4") (pintype "passive"))
      (node (ref "JP2") (pin "5") (pinfunction "5_5") (pintype "passive"))
      (node (ref "JP2") (pin "6") (pinfunction "6_6") (pintype "passive"))
      (node (ref "JP2") (pin "7") (pinfunction "7_7") (pintype "passive"))
      (node (ref "JP_PI") (pin "1") (pinfunction "1_1") (pintype "passive"))
      (node (ref "L1") (pin "2") (pinfunction "2_2") (pintype "passive"))
      (node (ref "R4") (pin "2") (pinfunction "2_2") (pintype "passive"))
      (node (ref "RP12") (pin "5") (pinfunction "5_5") (pintype "passive"))
      (node (ref "RP12") (pin "6") (pinfunction "6_6") (pintype "passive"))
      (node (ref "RP12") (pin "7") (pinfunction "7_7") (pintype "passive"))
      (node (ref "RP12") (pin "8") (pinfunction "8_8") (pintype "passive"))
      (node (ref "RP34") (pin "5") (pinfunction "5_5") (pintype "passive"))
      (node (ref "RP34") (pin "6") (pinfunction "6_6") (pintype "passive"))
      (node (ref "RP34") (pin "7") (pinfunction "7_7") (pintype "passive"))
      (node (ref "RP34") (pin "8") (pinfunction "8_8") (pintype "passive"))
      (node (ref "U4") (pin "19") (pinfunction "STBY_19") (pintype "passive"))
      (node (ref "U4") (pin "20") (pinfunction "VCC_20") (pintype "passive"))
      (node (ref "U5") (pin "19") (pinfunction "STBY_19") (pintype "passive"))
      (node (ref "U5") (pin "20") (pinfunction "VCC_20") (pintype "passive"))
    )
    (net (code "92") (name "VCC12V") (class "Default")
      (node (ref "C1") (pin "2") (pinfunction "2_2") (pintype "passive"))
      (node (ref "C13") (pin "2") (pinfunction "2_2") (pintype "passive"))
      (node (ref "C14") (pin "2") (pinfunction "2_2") (pintype "passive"))
      (node (ref "C15") (pin "2") (pinfunction "2_2") (pintype "passive"))
      (node (ref "C16") (pin "2") (pinfunction "2_2") (pintype "passive"))
      (node (ref "C2") (pin "2") (pinfunction "2_2") (pintype "passive"))
      (node (ref "C3") (pin "2") (pinfunction "2_2") (pintype "passive"))
      (node (ref "D1") (pin "2") (pinfunction "K_2") (pintype "passive"))
      (node (ref "MP2225") (pin "2") (pinfunction "IN_2") (pintype "power_in"))
      (node (ref "R1") (pin "1") (pinfunction "1_1") (pintype "passive"))
      (node (ref "R18") (pin "2") (pinfunction "2_2") (pintype "passive"))
      (node (ref "S1") (pin "2") (pinfunction "2_2") (pintype "passive"))
      (node (ref "U4") (pin "13") (pinfunction "VM2_13") (pintype "passive"))
      (node (ref "U4") (pin "14") (pinfunction "VM3_14") (pintype "passive"))
      (node (ref "U4") (pin "24") (pinfunction "VM1_24") (pintype "passive"))
      (node (ref "U5") (pin "13") (pinfunction "VM2_13") (pintype "passive"))
      (node (ref "U5") (pin "14") (pinfunction "VM3_14") (pintype "passive"))
      (node (ref "U5") (pin "24") (pinfunction "VM1_24") (pintype "passive"))
    )
    (net (code "93") (name "unconnected-(S1-Pad3)") (class "Default")
      (node (ref "S1") (pin "3") (pinfunction "3_3") (pintype "passive"))
    )
    (net (code "94") (name "unconnected-(U1-*SUSPEND-Pad11)") (class "Default")
      (node (ref "U1") (pin "11") (pinfunction "*SUSPEND_11") (pintype "passive"))
    )
    (net (code "95") (name "unconnected-(U1-CTS-Pad23)") (class "Default")
      (node (ref "U1") (pin "23") (pinfunction "CTS_23") (pintype "passive"))
    )
    (net (code "96") (name "unconnected-(U1-DCD-Pad1)") (class "Default")
      (node (ref "U1") (pin "1") (pinfunction "DCD_1") (pintype "passive"))
    )
    (net (code "97") (name "unconnected-(U1-DSR-Pad27)") (class "Default")
      (node (ref "U1") (pin "27") (pinfunction "DSR_27") (pintype "passive"))
    )
    (net (code "98") (name "unconnected-(U1-NC-Pad10)") (class "Default")
      (node (ref "U1") (pin "10") (pinfunction "NC_10") (pintype "passive"))
    )
    (net (code "99") (name "unconnected-(U1-NC-Pad13)") (class "Default")
      (node (ref "U1") (pin "13") (pinfunction "NC_13") (pintype "passive"))
    )
    (net (code "100") (name "unconnected-(U1-NC-Pad14)") (class "Default")
      (node (ref "U1") (pin "14") (pinfunction "NC_14") (pintype "passive"))
    )
    (net (code "101") (name "unconnected-(U1-NC-Pad15)") (class "Default")
      (node (ref "U1") (pin "15") (pinfunction "NC_15") (pintype "passive"))
    )
    (net (code "102") (name "unconnected-(U1-NC-Pad16)") (class "Default")
      (node (ref "U1") (pin "16") (pinfunction "NC_16") (pintype "passive"))
    )
    (net (code "103") (name "unconnected-(U1-NC-Pad17)") (class "Default")
      (node (ref "U1") (pin "17") (pinfunction "NC_17") (pintype "passive"))
    )
    (net (code "104") (name "unconnected-(U1-NC-Pad18)") (class "Default")
      (node (ref "U1") (pin "18") (pinfunction "NC_18") (pintype "passive"))
    )
    (net (code "105") (name "unconnected-(U1-NC-Pad19)") (class "Default")
      (node (ref "U1") (pin "19") (pinfunction "NC_19") (pintype "passive"))
    )
    (net (code "106") (name "unconnected-(U1-NC-Pad20)") (class "Default")
      (node (ref "U1") (pin "20") (pinfunction "NC_20") (pintype "passive"))
    )
    (net (code "107") (name "unconnected-(U1-NC-Pad21)") (class "Default")
      (node (ref "U1") (pin "21") (pinfunction "NC_21") (pintype "passive"))
    )
    (net (code "108") (name "unconnected-(U1-NC-Pad22)") (class "Default")
      (node (ref "U1") (pin "22") (pinfunction "NC_22") (pintype "passive"))
    )
    (net (code "109") (name "unconnected-(U1-RI-Pad2)") (class "Default")
      (node (ref "U1") (pin "2") (pinfunction "RI_2") (pintype "passive"))
    )
    (net (code "110") (name "unconnected-(U1-SUSPEND-Pad12)") (class "Default")
      (node (ref "U1") (pin "12") (pinfunction "SUSPEND_12") (pintype "passive"))
    )
    (net (code "111") (name "unconnected-(U1-VDD-Pad6)") (class "Default")
      (node (ref "U1") (pin "6") (pinfunction "VDD_6") (pintype "passive"))
    )
    (net (code "112") (name "unconnected-(U3-A_CL-Pad7)") (class "Default")
      (node (ref "U3") (pin "7") (pinfunction "A_CL_7") (pintype "passive+no_connect"))
    )
    (net (code "113") (name "unconnected-(U3-A_DA-Pad6)") (class "Default")
      (node (ref "U3") (pin "6") (pinfunction "A_DA_6") (pintype "passive+no_connect"))
    )
    (net (code "114") (name "unconnected-(U3-CLKOUT-Pad22)") (class "Default")
      (node (ref "U3") (pin "22") (pinfunction "CLKOUT_22") (pintype "passive+no_connect"))
    )
    (net (code "115") (name "unconnected-(U3-NC-Pad2)") (class "Default")
      (node (ref "U3") (pin "2") (pinfunction "NC_2") (pintype "passive+no_connect"))
    )
    (net (code "116") (name "unconnected-(U3-NC-Pad3)") (class "Default")
      (node (ref "U3") (pin "3") (pinfunction "NC_3") (pintype "passive+no_connect"))
    )
    (net (code "117") (name "unconnected-(U3-NC-Pad4)") (class "Default")
      (node (ref "U3") (pin "4") (pinfunction "NC_4") (pintype "passive+no_connect"))
    )
    (net (code "118") (name "unconnected-(U3-NC-Pad5)") (class "Default")
      (node (ref "U3") (pin "5") (pinfunction "NC_5") (pintype "passive+no_connect"))
    )
    (net (code "119") (name "unconnected-(U3-NC-Pad14)") (class "Default")
      (node (ref "U3") (pin "14") (pinfunction "NC_14") (pintype "passive"))
    )
    (net (code "120") (name "unconnected-(U3-NC-Pad15)") (class "Default")
      (node (ref "U3") (pin "15") (pinfunction "NC_15") (pintype "passive"))
    )
    (net (code "121") (name "unconnected-(U3-NC-Pad16)") (class "Default")
      (node (ref "U3") (pin "16") (pinfunction "NC_16") (pintype "passive"))
    )
    (net (code "122") (name "unconnected-(U3-NC-Pad17)") (class "Default")
      (node (ref "U3") (pin "17") (pinfunction "NC_17") (pintype "passive"))
    )
    (net (code "123") (name "unconnected-(U3-RESV-Pad19)") (class "Default")
      (node (ref "U3") (pin "19") (pinfunction "RESV_19") (pintype "passive+no_connect"))
    )
    (net (code "124") (name "unconnected-(U3-RESV-Pad21)") (class "Default")
      (node (ref "U3") (pin "21") (pinfunction "RESV_21") (pintype "passive+no_connect"))
    )
    (net (code "125") (name "unconnected-(USB1-RX1+-PadB11)") (class "Default")
      (node (ref "USB1") (pin "B11") (pinfunction "RX1+_B11") (pintype "passive"))
    )
    (net (code "126") (name "unconnected-(USB1-RX1--PadB10)") (class "Default")
      (node (ref "USB1") (pin "B10") (pinfunction "RX1-_B10") (pintype "passive"))
    )
    (net (code "127") (name "unconnected-(USB1-RX2+-PadA11)") (class "Default")
      (node (ref "USB1") (pin "A11") (pinfunction "RX2+_A11") (pintype "passive"))
    )
    (net (code "128") (name "unconnected-(USB1-RX2--PadA10)") (class "Default")
      (node (ref "USB1") (pin "A10") (pinfunction "RX2-_A10") (pintype "passive"))
    )
    (net (code "129") (name "unconnected-(USB1-SBU1-PadA8)") (class "Default")
      (node (ref "USB1") (pin "A8") (pinfunction "SBU1_A8") (pintype "passive"))
    )
    (net (code "130") (name "unconnected-(USB1-SBU2-PadB8)") (class "Default")
      (node (ref "USB1") (pin "B8") (pinfunction "SBU2_B8") (pintype "passive"))
    )
    (net (code "131") (name "unconnected-(USB1-TX1+-PadA2)") (class "Default")
      (node (ref "USB1") (pin "A2") (pinfunction "TX1+_A2") (pintype "passive"))
    )
    (net (code "132") (name "unconnected-(USB1-TX1--PadA3)") (class "Default")
      (node (ref "USB1") (pin "A3") (pinfunction "TX1-_A3") (pintype "passive"))
    )
    (net (code "133") (name "unconnected-(USB1-TX2+-PadB2)") (class "Default")
      (node (ref "USB1") (pin "B2") (pinfunction "TX2+_B2") (pintype "passive"))
    )
    (net (code "134") (name "unconnected-(USB1-TX2--PadB3)") (class "Default")
      (node (ref "USB1") (pin "B3") (pinfunction "TX2-_B3") (pintype "passive"))
    )
  )
)
